# QuickPSoC3V2_LongPads_04042012.net
KiCad netlist of a schematic drawn in EAGLE
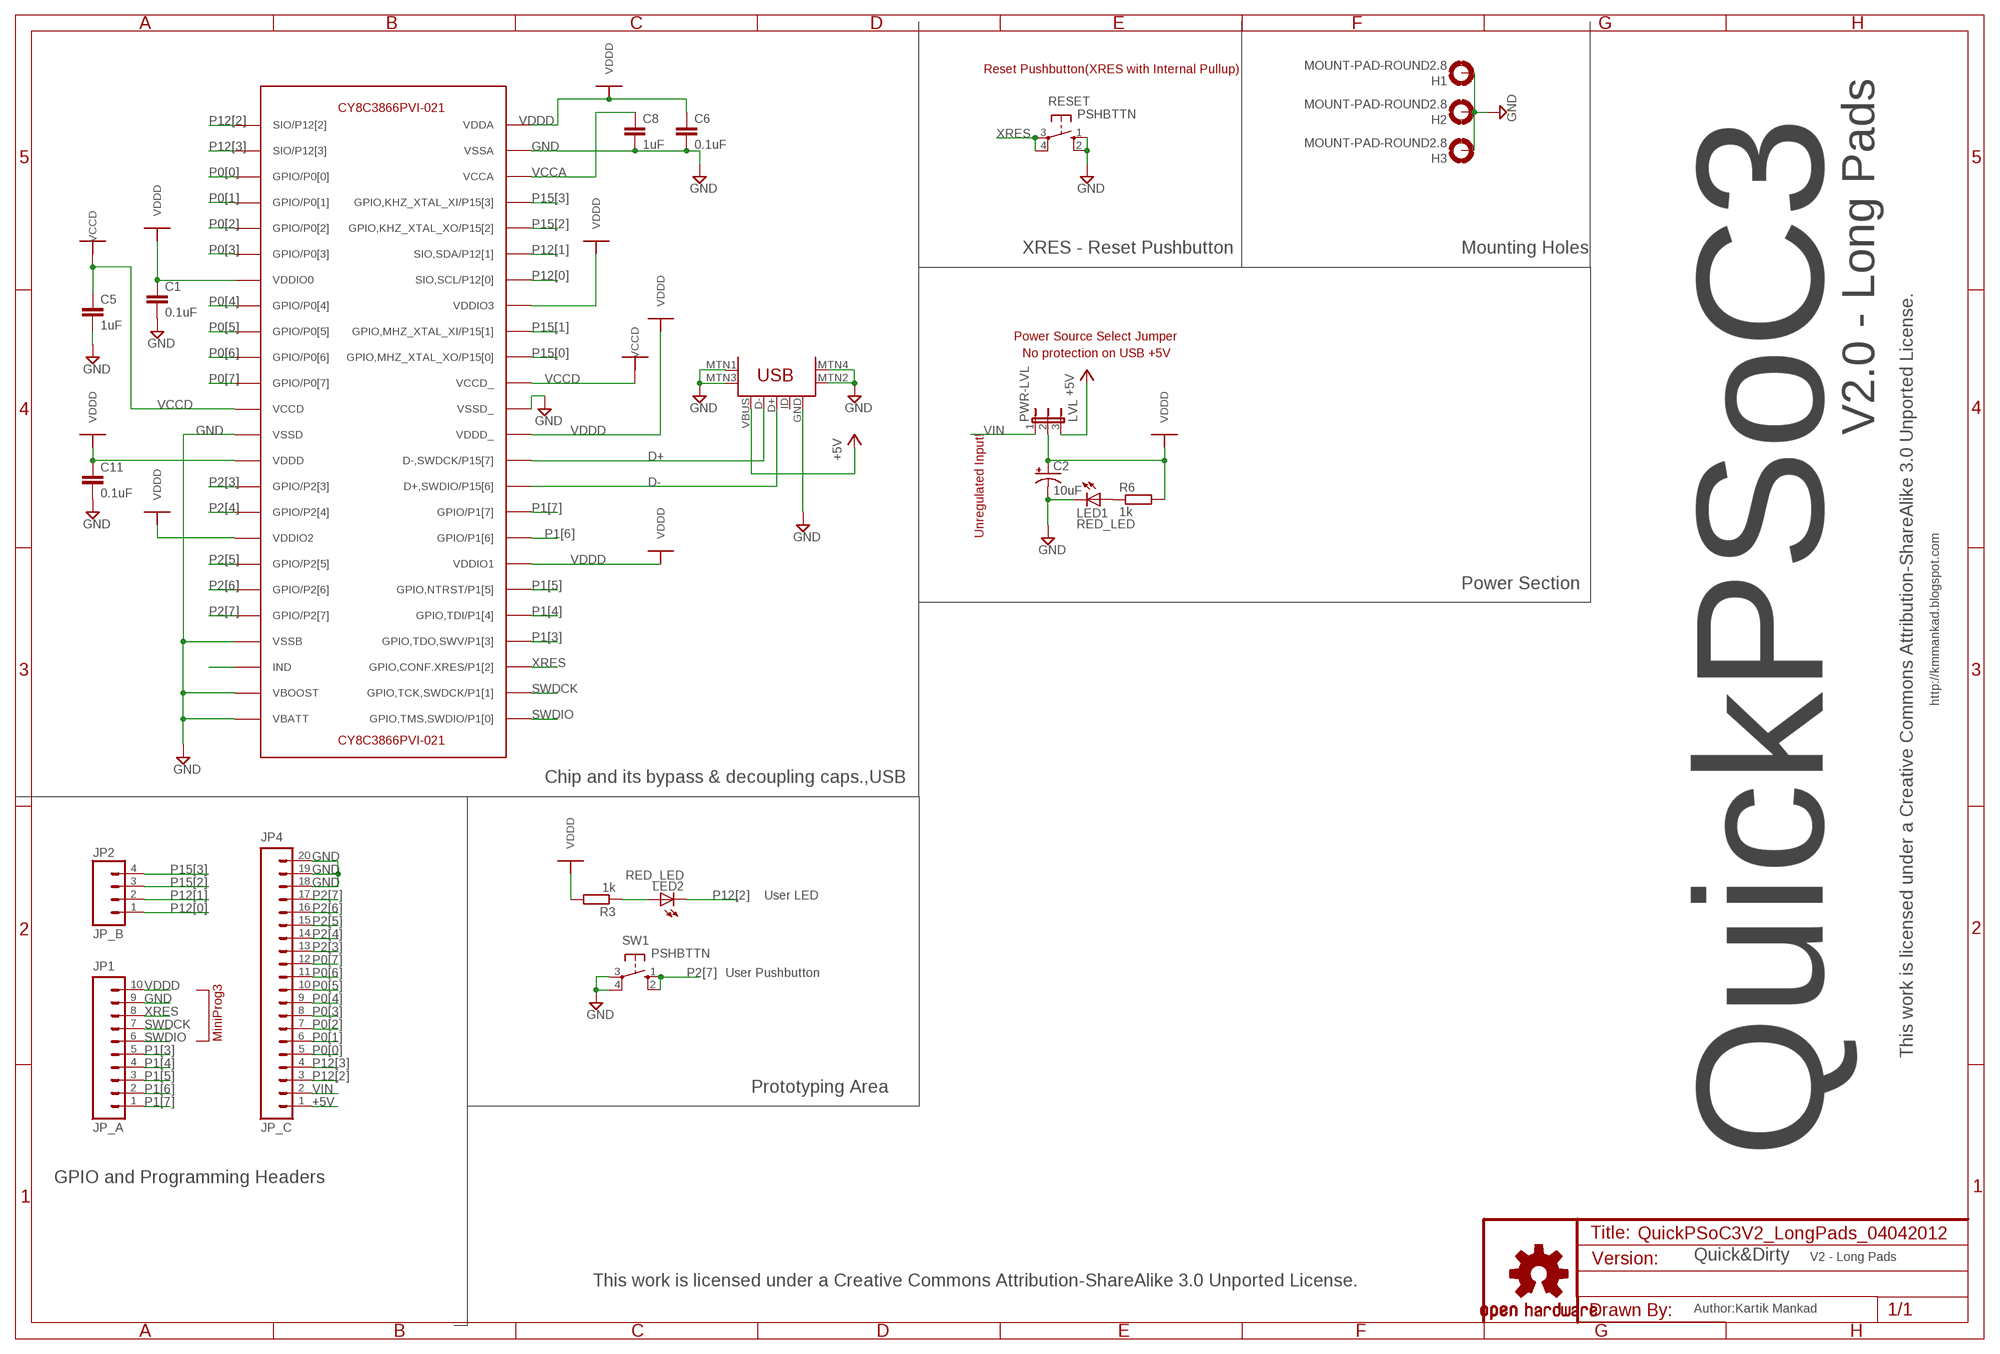
[diagram p0: schematic, sheet 1]

(export (version "E")
  (design (tool "Eeschema 10.0.6"))
  (components
    (comp (ref "C1")
      (value "0.1uF")
      (footprint "eagle-import:C0805K")
      (libsource (lib "eagle-import") (part "C-EUC0805K"))
    )
    (comp (ref "C2")
      (value "10uF")
      (footprint "eagle-import:CPOL-RADIAL-10UF-25V")
      (libsource (lib "eagle-import") (part "CAP_POLPTH2"))
    )
    (comp (ref "C5")
      (value "1uF")
      (footprint "eagle-import:C0805K")
      (libsource (lib "eagle-import") (part "C-EUC0805K"))
    )
    (comp (ref "C6")
      (value "0.1uF")
      (footprint "eagle-import:C0805K")
      (libsource (lib "eagle-import") (part "C-EUC0805K"))
    )
    (comp (ref "C8")
      (value "1uF")
      (footprint "eagle-import:C0805K")
      (libsource (lib "eagle-import") (part "C-EUC0805K"))
    )
    (comp (ref "C11")
      (value "0.1uF")
      (footprint "eagle-import:C0805K")
      (libsource (lib "eagle-import") (part "C-EUC0805K"))
    )
    (comp (ref "H1")
      (value "MOUNT-PAD-ROUND2.8")
      (footprint "eagle-import:2,8-PAD")
      (libsource (lib "eagle-import") (part "MOUNT-PAD-ROUND2.8"))
    )
    (comp (ref "H2")
      (value "MOUNT-PAD-ROUND2.8")
      (footprint "eagle-import:2,8-PAD")
      (libsource (lib "eagle-import") (part "MOUNT-PAD-ROUND2.8"))
    )
    (comp (ref "H3")
      (value "MOUNT-PAD-ROUND2.8")
      (footprint "eagle-import:2,8-PAD")
      (libsource (lib "eagle-import") (part "MOUNT-PAD-ROUND2.8"))
    )
    (comp (ref "JP1")
      (value "JP_A")
      (footprint "eagle-import:1X10")
      (libsource (lib "eagle-import") (part "M10{dblquote}"))
    )
    (comp (ref "JP2")
      (value "JP_B")
      (footprint "eagle-import:1X04")
      (libsource (lib "eagle-import") (part "M04PTH"))
    )
    (comp (ref "JP4")
      (value "JP_C")
      (footprint "eagle-import:1X20")
      (libsource (lib "eagle-import") (part "M20"))
    )
    (comp (ref "LED1")
      (value "RED_LED")
      (footprint "eagle-import:LED-1206")
      (libsource (lib "eagle-import") (part "LED1206"))
    )
    (comp (ref "LED2")
      (value "RED_LED")
      (footprint "eagle-import:LED-1206")
      (libsource (lib "eagle-import") (part "LED1206"))
    )
    (comp (ref "PWR-LVL")
      (value "LVL")
      (footprint "eagle-import:JP2")
      (libsource (lib "eagle-import") (part "JP2E"))
    )
    (comp (ref "R3")
      (value "1k")
      (footprint "eagle-import:M0805")
      (libsource (lib "eagle-import") (part "R-EU_M0805"))
    )
    (comp (ref "R6")
      (value "1k")
      (footprint "eagle-import:M0805")
      (libsource (lib "eagle-import") (part "R-EU_M0805"))
    )
    (comp (ref "RESET")
      (value "PSHBTTN")
      (footprint "eagle-import:B3F-10XX")
      (libsource (lib "eagle-import") (part "10-XX"))
    )
    (comp (ref "SW1")
      (value "PSHBTTN")
      (footprint "eagle-import:B3F-10XX")
      (libsource (lib "eagle-import") (part "10-XX"))
    )
    (comp (ref "U$1")
      (value "CY8C3866PVI-021")
      (footprint "eagle-import:SSOP48DL")
      (libsource (lib "eagle-import") (part "CY8C3866PVI-021"))
    )
    (comp (ref "U$2")
      (value "OSHW-LOGOL")
      (footprint "eagle-import:OSHW-LOGO-L")
      (libsource (lib "eagle-import") (part "OSHW-LOGOL"))
    )
    (comp (ref "X1")
      (value "USB-MINIB-5PIN")
      (footprint "eagle-import:USB-MINIB")
      (libsource (lib "eagle-import") (part "USB-MINIB-5PIN"))
    )
  )
  (nets
    (net (code "1") (name "+5V") (class "Default")
      (node (ref "JP4") (pin "1") (pinfunction "1_1") (pintype "passive"))
      (node (ref "PWR-LVL") (pin "3") (pinfunction "3_3") (pintype "passive"))
      (node (ref "X1") (pin "VBUS") (pinfunction "VBUS_VBUS") (pintype "bidirectional"))
    )
    (net (code "2") (name "/D+") (class "Default")
      (node (ref "U$1") (pin "35") (pinfunction "D-,SWDCK/P15[7]_35") (pintype "bidirectional"))
      (node (ref "X1") (pin "D-") (pinfunction "D-_D-") (pintype "bidirectional"))
    )
    (net (code "3") (name "/D-") (class "Default")
      (node (ref "U$1") (pin "34") (pinfunction "D+,SWDIO/P15[6]_34") (pintype "bidirectional"))
      (node (ref "X1") (pin "D+") (pinfunction "D+_D+") (pintype "bidirectional"))
    )
    (net (code "4") (name "/P0[0]") (class "Default")
      (node (ref "JP4") (pin "5") (pinfunction "5_5") (pintype "passive"))
      (node (ref "U$1") (pin "3") (pinfunction "GPIO/P0[0]_3") (pintype "bidirectional"))
    )
    (net (code "5") (name "/P0[1]") (class "Default")
      (node (ref "JP4") (pin "6") (pinfunction "6_6") (pintype "passive"))
      (node (ref "U$1") (pin "4") (pinfunction "GPIO/P0[1]_4") (pintype "bidirectional"))
    )
    (net (code "6") (name "/P0[2]") (class "Default")
      (node (ref "JP4") (pin "7") (pinfunction "7_7") (pintype "passive"))
      (node (ref "U$1") (pin "5") (pinfunction "GPIO/P0[2]_5") (pintype "bidirectional"))
    )
    (net (code "7") (name "/P0[3]") (class "Default")
      (node (ref "JP4") (pin "8") (pinfunction "8_8") (pintype "passive"))
      (node (ref "U$1") (pin "6") (pinfunction "GPIO/P0[3]_6") (pintype "bidirectional"))
    )
    (net (code "8") (name "/P0[4]") (class "Default")
      (node (ref "JP4") (pin "9") (pinfunction "9_9") (pintype "passive"))
      (node (ref "U$1") (pin "8") (pinfunction "GPIO/P0[4]_8") (pintype "bidirectional"))
    )
    (net (code "9") (name "/P0[5]") (class "Default")
      (node (ref "JP4") (pin "10") (pinfunction "10_10") (pintype "passive"))
      (node (ref "U$1") (pin "9") (pinfunction "GPIO/P0[5]_9") (pintype "bidirectional"))
    )
    (net (code "10") (name "/P0[6]") (class "Default")
      (node (ref "JP4") (pin "11") (pinfunction "11_11") (pintype "passive"))
      (node (ref "U$1") (pin "10") (pinfunction "GPIO/P0[6]_10") (pintype "bidirectional"))
    )
    (net (code "11") (name "/P0[7]") (class "Default")
      (node (ref "JP4") (pin "12") (pinfunction "12_12") (pintype "passive"))
      (node (ref "U$1") (pin "11") (pinfunction "GPIO/P0[7]_11") (pintype "bidirectional"))
    )
    (net (code "12") (name "/P1[3]") (class "Default")
      (node (ref "JP1") (pin "5") (pinfunction "5_5") (pintype "passive"))
      (node (ref "U$1") (pin "28") (pinfunction "GPIO,TDO,SWV/P1[3]_28") (pintype "bidirectional"))
    )
    (net (code "13") (name "/P1[4]") (class "Default")
      (node (ref "JP1") (pin "4") (pinfunction "4_4") (pintype "passive"))
      (node (ref "U$1") (pin "29") (pinfunction "GPIO,TDI/P1[4]_29") (pintype "bidirectional"))
    )
    (net (code "14") (name "/P1[5]") (class "Default")
      (node (ref "JP1") (pin "3") (pinfunction "3_3") (pintype "passive"))
      (node (ref "U$1") (pin "30") (pinfunction "GPIO,NTRST/P1[5]_30") (pintype "bidirectional"))
    )
    (net (code "15") (name "/P1[6]") (class "Default")
      (node (ref "JP1") (pin "2") (pinfunction "2_2") (pintype "passive"))
      (node (ref "U$1") (pin "32") (pinfunction "GPIO/P1[6]_32") (pintype "bidirectional"))
    )
    (net (code "16") (name "/P1[7]") (class "Default")
      (node (ref "JP1") (pin "1") (pinfunction "1_1") (pintype "passive"))
      (node (ref "U$1") (pin "33") (pinfunction "GPIO/P1[7]_33") (pintype "bidirectional"))
    )
    (net (code "17") (name "/P2[3]") (class "Default")
      (node (ref "JP4") (pin "13") (pinfunction "13_13") (pintype "passive"))
      (node (ref "U$1") (pin "15") (pinfunction "GPIO/P2[3]_15") (pintype "bidirectional"))
    )
    (net (code "18") (name "/P2[4]") (class "Default")
      (node (ref "JP4") (pin "14") (pinfunction "14_14") (pintype "passive"))
      (node (ref "U$1") (pin "16") (pinfunction "GPIO/P2[4]_16") (pintype "bidirectional"))
    )
    (net (code "19") (name "/P2[5]") (class "Default")
      (node (ref "JP4") (pin "15") (pinfunction "15_15") (pintype "passive"))
      (node (ref "U$1") (pin "18") (pinfunction "GPIO/P2[5]_18") (pintype "bidirectional"))
    )
    (net (code "20") (name "/P2[6]") (class "Default")
      (node (ref "JP4") (pin "16") (pinfunction "16_16") (pintype "passive"))
      (node (ref "U$1") (pin "19") (pinfunction "GPIO/P2[6]_19") (pintype "bidirectional"))
    )
    (net (code "21") (name "/P2[7]") (class "Default")
      (node (ref "JP4") (pin "17") (pinfunction "17_17") (pintype "passive"))
      (node (ref "SW1") (pin "1") (pinfunction "S_1") (pintype "passive"))
      (node (ref "SW1") (pin "2") (pinfunction "S1_2") (pintype "passive"))
      (node (ref "U$1") (pin "20") (pinfunction "GPIO/P2[7]_20") (pintype "bidirectional"))
    )
    (net (code "22") (name "/P12[0]") (class "Default")
      (node (ref "JP2") (pin "1") (pinfunction "1_1") (pintype "passive"))
      (node (ref "U$1") (pin "42") (pinfunction "SIO,SCL/P12[0]_42") (pintype "output"))
    )
    (net (code "23") (name "/P12[1]") (class "Default")
      (node (ref "JP2") (pin "2") (pinfunction "2_2") (pintype "passive"))
      (node (ref "U$1") (pin "43") (pinfunction "SIO,SDA/P12[1]_43") (pintype "bidirectional"))
    )
    (net (code "24") (name "/P12[2]") (class "Default")
      (node (ref "JP4") (pin "3") (pinfunction "3_3") (pintype "passive"))
      (node (ref "LED2") (pin "C") (pinfunction "C_C") (pintype "passive"))
      (node (ref "U$1") (pin "1") (pinfunction "SIO/P12[2]_1") (pintype "bidirectional"))
    )
    (net (code "25") (name "/P12[3]") (class "Default")
      (node (ref "JP4") (pin "4") (pinfunction "4_4") (pintype "passive"))
      (node (ref "U$1") (pin "2") (pinfunction "SIO/P12[3]_2") (pintype "bidirectional"))
    )
    (net (code "26") (name "/P15[0]") (class "Default")
      (node (ref "U$1") (pin "39") (pinfunction "GPIO,MHZ_XTAL_XO/P15[0]_39") (pintype "bidirectional"))
    )
    (net (code "27") (name "/P15[1]") (class "Default")
      (node (ref "U$1") (pin "40") (pinfunction "GPIO,MHZ_XTAL_XI/P15[1]_40") (pintype "bidirectional"))
    )
    (net (code "28") (name "/P15[2]") (class "Default")
      (node (ref "JP2") (pin "3") (pinfunction "3_3") (pintype "passive"))
      (node (ref "U$1") (pin "44") (pinfunction "GPIO,KHZ_XTAL_XO/P15[2]_44") (pintype "bidirectional"))
    )
    (net (code "29") (name "/P15[3]") (class "Default")
      (node (ref "JP2") (pin "4") (pinfunction "4_4") (pintype "passive"))
      (node (ref "U$1") (pin "45") (pinfunction "GPIO,KHZ_XTAL_XI/P15[3]_45") (pintype "bidirectional"))
    )
    (net (code "30") (name "/SWDCK") (class "Default")
      (node (ref "JP1") (pin "7") (pinfunction "7_7") (pintype "passive"))
      (node (ref "U$1") (pin "26") (pinfunction "GPIO,TCK,SWDCK/P1[1]_26") (pintype "bidirectional"))
    )
    (net (code "31") (name "/SWDIO") (class "Default")
      (node (ref "JP1") (pin "6") (pinfunction "6_6") (pintype "passive"))
      (node (ref "U$1") (pin "25") (pinfunction "GPIO,TMS,SWDIO/P1[0]_25") (pintype "bidirectional"))
    )
    (net (code "32") (name "/VCCA") (class "Default")
      (node (ref "C8") (pin "1") (pinfunction "1_1") (pintype "passive"))
      (node (ref "U$1") (pin "46") (pinfunction "VCCA_46") (pintype "bidirectional"))
    )
    (net (code "33") (name "/VIN") (class "Default")
      (node (ref "JP4") (pin "2") (pinfunction "2_2") (pintype "passive"))
      (node (ref "PWR-LVL") (pin "1") (pinfunction "1_1") (pintype "passive"))
    )
    (net (code "34") (name "/XRES") (class "Default")
      (node (ref "JP1") (pin "8") (pinfunction "8_8") (pintype "passive"))
      (node (ref "RESET") (pin "3") (pinfunction "P_3") (pintype "passive"))
      (node (ref "RESET") (pin "4") (pinfunction "P1_4") (pintype "passive"))
      (node (ref "U$1") (pin "27") (pinfunction "GPIO,CONF.XRES/P1[2]_27") (pintype "bidirectional"))
    )
    (net (code "35") (name "GND") (class "Default")
      (node (ref "C1") (pin "2") (pinfunction "2_2") (pintype "passive"))
      (node (ref "C11") (pin "2") (pinfunction "2_2") (pintype "passive"))
      (node (ref "C2") (pin "2") (pinfunction "-_2") (pintype "passive"))
      (node (ref "C5") (pin "2") (pinfunction "2_2") (pintype "passive"))
      (node (ref "C6") (pin "2") (pinfunction "2_2") (pintype "passive"))
      (node (ref "C8") (pin "2") (pinfunction "2_2") (pintype "passive"))
      (node (ref "H1") (pin "B2,8") (pinfunction "MOUNT_B2,8") (pintype "passive"))
      (node (ref "H2") (pin "B2,8") (pinfunction "MOUNT_B2,8") (pintype "passive"))
      (node (ref "H3") (pin "B2,8") (pinfunction "MOUNT_B2,8") (pintype "passive"))
      (node (ref "JP1") (pin "9") (pinfunction "9_9") (pintype "passive"))
      (node (ref "JP4") (pin "18") (pinfunction "18_18") (pintype "passive"))
      (node (ref "JP4") (pin "19") (pinfunction "19_19") (pintype "passive"))
      (node (ref "JP4") (pin "20") (pinfunction "20_20") (pintype "passive"))
      (node (ref "LED1") (pin "C") (pinfunction "C_C") (pintype "passive"))
      (node (ref "RESET") (pin "1") (pinfunction "S_1") (pintype "passive"))
      (node (ref "RESET") (pin "2") (pinfunction "S1_2") (pintype "passive"))
      (node (ref "SW1") (pin "3") (pinfunction "P_3") (pintype "passive"))
      (node (ref "SW1") (pin "4") (pinfunction "P1_4") (pintype "passive"))
      (node (ref "U$1") (pin "13") (pinfunction "VSSD_13") (pintype "power_in"))
      (node (ref "U$1") (pin "21") (pinfunction "VSSB_21") (pintype "power_in"))
      (node (ref "U$1") (pin "23") (pinfunction "VBOOST_23") (pintype "bidirectional"))
      (node (ref "U$1") (pin "24") (pinfunction "VBATT_24") (pintype "bidirectional"))
      (node (ref "U$1") (pin "37") (pinfunction "VSSD__37") (pintype "bidirectional"))
      (node (ref "U$1") (pin "47") (pinfunction "VSSA_47") (pintype "bidirectional"))
      (node (ref "X1") (pin "GND") (pinfunction "GND_GND") (pintype "bidirectional"))
      (node (ref "X1") (pin "MTN1") (pinfunction "MTN2_MTN1") (pintype "bidirectional"))
      (node (ref "X1") (pin "MTN2") (pinfunction "MTN3_MTN2") (pintype "bidirectional"))
      (node (ref "X1") (pin "MTN3") (pinfunction "MTN1_MTN3") (pintype "bidirectional"))
      (node (ref "X1") (pin "MTN4") (pinfunction "MTN4_MTN4") (pintype "bidirectional"))
    )
    (net (code "36") (name "Net-(LED1-PadA)") (class "Default")
      (node (ref "LED1") (pin "A") (pinfunction "A_A") (pintype "passive"))
      (node (ref "R6") (pin "1") (pinfunction "1_1") (pintype "passive"))
    )
    (net (code "37") (name "Net-(LED2-PadA)") (class "Default")
      (node (ref "LED2") (pin "A") (pinfunction "A_A") (pintype "passive"))
      (node (ref "R3") (pin "1") (pinfunction "1_1") (pintype "passive"))
    )
    (net (code "38") (name "VCCD") (class "Default")
      (node (ref "C5") (pin "1") (pinfunction "1_1") (pintype "passive"))
      (node (ref "U$1") (pin "12") (pinfunction "VCCD_12") (pintype "power_in"))
      (node (ref "U$1") (pin "38") (pinfunction "VCCD__38") (pintype "bidirectional"))
    )
    (net (code "39") (name "VDDD") (class "Default")
      (node (ref "C1") (pin "1") (pinfunction "1_1") (pintype "passive"))
      (node (ref "C11") (pin "1") (pinfunction "1_1") (pintype "passive"))
      (node (ref "C2") (pin "1") (pinfunction "+_1") (pintype "passive"))
      (node (ref "C6") (pin "1") (pinfunction "1_1") (pintype "passive"))
      (node (ref "JP1") (pin "10") (pinfunction "10_10") (pintype "passive"))
      (node (ref "PWR-LVL") (pin "2") (pinfunction "2_2") (pintype "passive"))
      (node (ref "R3") (pin "2") (pinfunction "2_2") (pintype "passive"))
      (node (ref "R6") (pin "2") (pinfunction "2_2") (pintype "passive"))
      (node (ref "U$1") (pin "14") (pinfunction "VDDD_14") (pintype "power_in"))
      (node (ref "U$1") (pin "17") (pinfunction "VDDIO2_17") (pintype "power_in"))
      (node (ref "U$1") (pin "31") (pinfunction "VDDIO1_31") (pintype "power_in"))
      (node (ref "U$1") (pin "36") (pinfunction "VDDD__36") (pintype "bidirectional"))
      (node (ref "U$1") (pin "41") (pinfunction "VDDIO3_41") (pintype "bidirectional"))
      (node (ref "U$1") (pin "48") (pinfunction "VDDA_48") (pintype "bidirectional"))
      (node (ref "U$1") (pin "7") (pinfunction "VDDIO0_7") (pintype "power_in"))
    )
    (net (code "40") (name "unconnected-(U$1-IND-Pad22)") (class "Default")
      (node (ref "U$1") (pin "22") (pinfunction "IND_22") (pintype "bidirectional"))
    )
    (net (code "41") (name "unconnected-(X1-PadID)") (class "Default")
      (node (ref "X1") (pin "ID") (pinfunction "ID_ID") (pintype "bidirectional"))
    )
  )
)
